# OSO-MISC-20-022_New_Blinky_Board_for_Rin.net
KiCad netlist of a schematic drawn in EAGLE
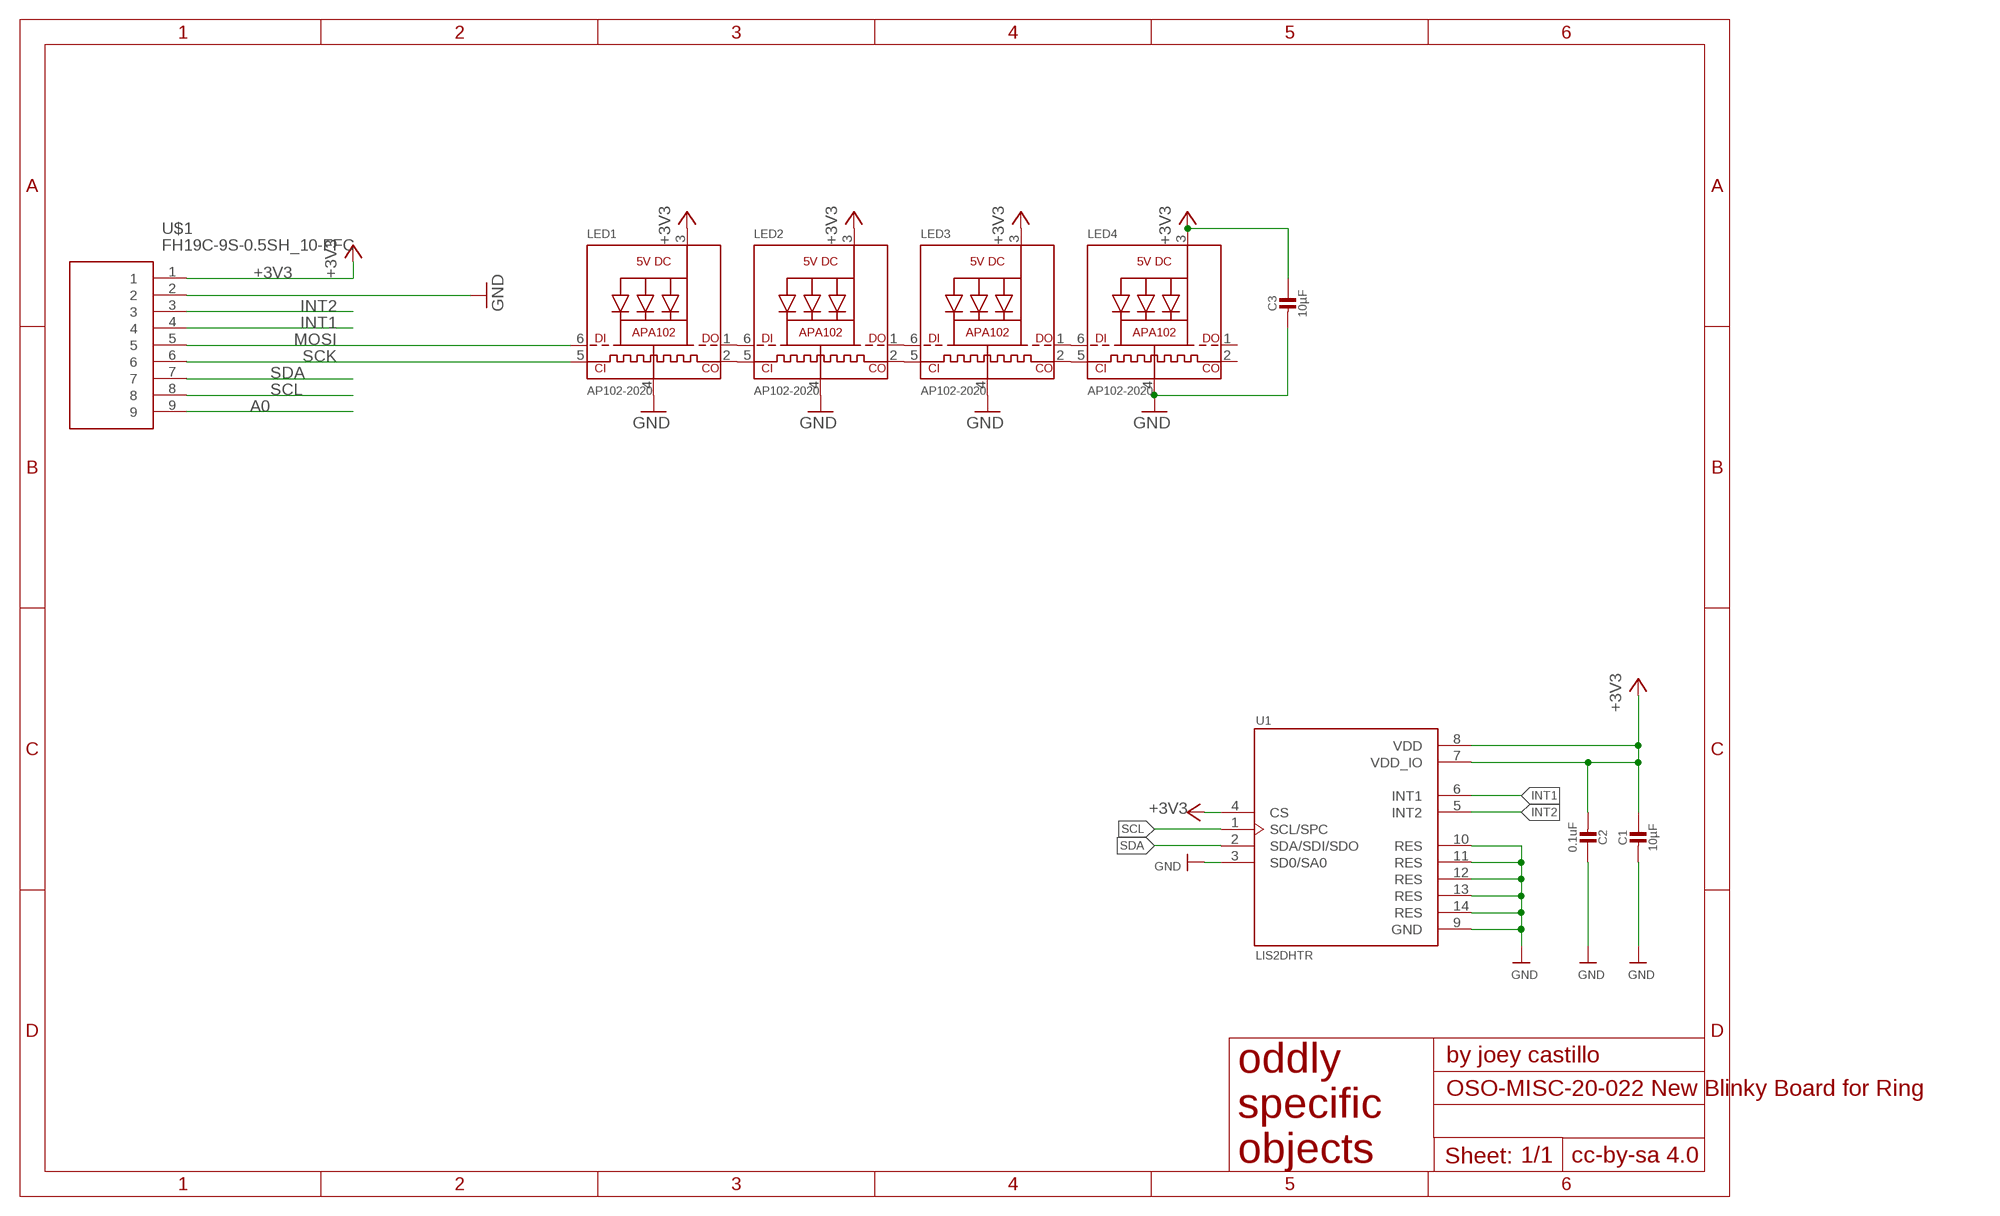
[diagram p0: schematic, sheet 1]

(export (version "E")
  (design (tool "Eeschema 10.0.6"))
  (components
    (comp (ref "C1")
      (value "10µF")
      (footprint "eagle-import:0805_10MGAP")
      (libsource (lib "eagle-import") (part "CAP_CERAMIC0805_10MGAP"))
    )
    (comp (ref "C2")
      (value "0.1uF")
      (footprint "eagle-import:0805-NO")
      (libsource (lib "eagle-import") (part "CAP_CERAMIC0805-NOOUTLINE"))
    )
    (comp (ref "C3")
      (value "10µF")
      (footprint "eagle-import:0805-NO")
      (libsource (lib "eagle-import") (part "CAP_CERAMIC0805-NOOUTLINE"))
    )
    (comp (ref "LED1")
      (value "AP102-2020")
      (footprint "eagle-import:APA102_2020")
      (libsource (lib "eagle-import") (part "APA1022020"))
    )
    (comp (ref "LED2")
      (value "AP102-2020")
      (footprint "eagle-import:APA102_2020")
      (libsource (lib "eagle-import") (part "APA1022020"))
    )
    (comp (ref "LED3")
      (value "AP102-2020")
      (footprint "eagle-import:APA102_2020")
      (libsource (lib "eagle-import") (part "APA1022020"))
    )
    (comp (ref "LED4")
      (value "AP102-2020")
      (footprint "eagle-import:APA102_2020")
      (libsource (lib "eagle-import") (part "APA1022020"))
    )
    (comp (ref "U$1")
      (value "FH19C-9S-0.5SH_10-FFC")
      (footprint "eagle-import:FH19C9S05SH10-FFC")
      (libsource (lib "eagle-import") (part "FH19C-9S-0.5SH_10-FFC"))
    )
    (comp (ref "U1")
      (value "LIS2DHTR")
      (footprint "eagle-import:PQFN35P200X200X100-14N")
      (fields (field (name "DIGI-KEY_PART_NUMBER") "497-13795-1-ND") (field (name "MF") "STMicroelectronics"))
      (libsource (lib "eagle-import") (part "LIS2DHTR"))
    )
  )
  (nets
    (net (code "1") (name "+3V3") (class "Default")
      (node (ref "C1") (pin "1") (pinfunction "1_1") (pintype "passive"))
      (node (ref "C2") (pin "2") (pinfunction "2_2") (pintype "passive"))
      (node (ref "C3") (pin "1") (pinfunction "1_1") (pintype "passive"))
      (node (ref "LED1") (pin "3") (pinfunction "VDD_3") (pintype "power_in"))
      (node (ref "LED2") (pin "3") (pinfunction "VDD_3") (pintype "power_in"))
      (node (ref "LED3") (pin "3") (pinfunction "VDD_3") (pintype "power_in"))
      (node (ref "LED4") (pin "3") (pinfunction "VDD_3") (pintype "power_in"))
      (node (ref "U$1") (pin "1") (pinfunction "1_1") (pintype "bidirectional"))
      (node (ref "U1") (pin "4") (pinfunction "CS_4") (pintype "input"))
      (node (ref "U1") (pin "7") (pinfunction "VDD_IO_7") (pintype "power_in"))
      (node (ref "U1") (pin "8") (pinfunction "VDD_8") (pintype "power_in"))
    )
    (net (code "2") (name "/A0") (class "Default")
      (node (ref "U$1") (pin "9") (pinfunction "9_9") (pintype "bidirectional"))
    )
    (net (code "3") (name "/MOSI") (class "Default")
      (node (ref "LED1") (pin "6") (pinfunction "DI_6") (pintype "input"))
      (node (ref "U$1") (pin "5") (pinfunction "5_5") (pintype "bidirectional"))
    )
    (net (code "4") (name "/SCK") (class "Default")
      (node (ref "LED1") (pin "5") (pinfunction "CKI_5") (pintype "input"))
      (node (ref "U$1") (pin "6") (pinfunction "6_6") (pintype "bidirectional"))
    )
    (net (code "5") (name "GND") (class "Default")
      (node (ref "C1") (pin "2") (pinfunction "2_2") (pintype "passive"))
      (node (ref "C2") (pin "1") (pinfunction "1_1") (pintype "passive"))
      (node (ref "C3") (pin "2") (pinfunction "2_2") (pintype "passive"))
      (node (ref "LED1") (pin "4") (pinfunction "GND_4") (pintype "power_in"))
      (node (ref "LED2") (pin "4") (pinfunction "GND_4") (pintype "power_in"))
      (node (ref "LED3") (pin "4") (pinfunction "GND_4") (pintype "power_in"))
      (node (ref "LED4") (pin "4") (pinfunction "GND_4") (pintype "power_in"))
      (node (ref "U$1") (pin "2") (pinfunction "2_2") (pintype "bidirectional"))
      (node (ref "U1") (pin "10") (pinfunction "RES_10") (pintype "power_in"))
      (node (ref "U1") (pin "11") (pinfunction "RES_11") (pintype "power_in"))
      (node (ref "U1") (pin "12") (pinfunction "RES_12") (pintype "power_in"))
      (node (ref "U1") (pin "13") (pinfunction "RES_13") (pintype "power_in"))
      (node (ref "U1") (pin "14") (pinfunction "RES_14") (pintype "power_in"))
      (node (ref "U1") (pin "3") (pinfunction "SD0/SA0_3") (pintype "output"))
      (node (ref "U1") (pin "9") (pinfunction "GND_9") (pintype "power_in"))
    )
    (net (code "6") (name "INT1") (class "Default")
      (node (ref "U$1") (pin "4") (pinfunction "4_4") (pintype "bidirectional"))
      (node (ref "U1") (pin "6") (pinfunction "INT1_6") (pintype "output"))
    )
    (net (code "7") (name "INT2") (class "Default")
      (node (ref "U$1") (pin "3") (pinfunction "3_3") (pintype "bidirectional"))
      (node (ref "U1") (pin "5") (pinfunction "INT2_5") (pintype "output"))
    )
    (net (code "8") (name "Net-(LED1-CKO)") (class "Default")
      (node (ref "LED1") (pin "2") (pinfunction "CKO_2") (pintype "output"))
      (node (ref "LED2") (pin "5") (pinfunction "CKI_5") (pintype "input"))
    )
    (net (code "9") (name "Net-(LED1-DO)") (class "Default")
      (node (ref "LED1") (pin "1") (pinfunction "DO_1") (pintype "output"))
      (node (ref "LED2") (pin "6") (pinfunction "DI_6") (pintype "input"))
    )
    (net (code "10") (name "Net-(LED2-CKO)") (class "Default")
      (node (ref "LED2") (pin "2") (pinfunction "CKO_2") (pintype "output"))
      (node (ref "LED3") (pin "5") (pinfunction "CKI_5") (pintype "input"))
    )
    (net (code "11") (name "Net-(LED2-DO)") (class "Default")
      (node (ref "LED2") (pin "1") (pinfunction "DO_1") (pintype "output"))
      (node (ref "LED3") (pin "6") (pinfunction "DI_6") (pintype "input"))
    )
    (net (code "12") (name "Net-(LED3-CKO)") (class "Default")
      (node (ref "LED3") (pin "2") (pinfunction "CKO_2") (pintype "output"))
      (node (ref "LED4") (pin "5") (pinfunction "CKI_5") (pintype "input"))
    )
    (net (code "13") (name "Net-(LED3-DO)") (class "Default")
      (node (ref "LED3") (pin "1") (pinfunction "DO_1") (pintype "output"))
      (node (ref "LED4") (pin "6") (pinfunction "DI_6") (pintype "input"))
    )
    (net (code "14") (name "SCL") (class "Default")
      (node (ref "U$1") (pin "8") (pinfunction "8_8") (pintype "bidirectional"))
      (node (ref "U1") (pin "1") (pinfunction "SCL/SPC_1") (pintype "input"))
    )
    (net (code "15") (name "SDA") (class "Default")
      (node (ref "U$1") (pin "7") (pinfunction "7_7") (pintype "bidirectional"))
      (node (ref "U1") (pin "2") (pinfunction "SDA/SDI/SDO_2") (pintype "bidirectional"))
    )
    (net (code "16") (name "unconnected-(LED4-CKO-Pad2)") (class "Default")
      (node (ref "LED4") (pin "2") (pinfunction "CKO_2") (pintype "output"))
    )
    (net (code "17") (name "unconnected-(LED4-DO-Pad1)") (class "Default")
      (node (ref "LED4") (pin "1") (pinfunction "DO_1") (pintype "output"))
    )
  )
)
